# RoboShield.net
KiCad netlist of a schematic drawn in EAGLE
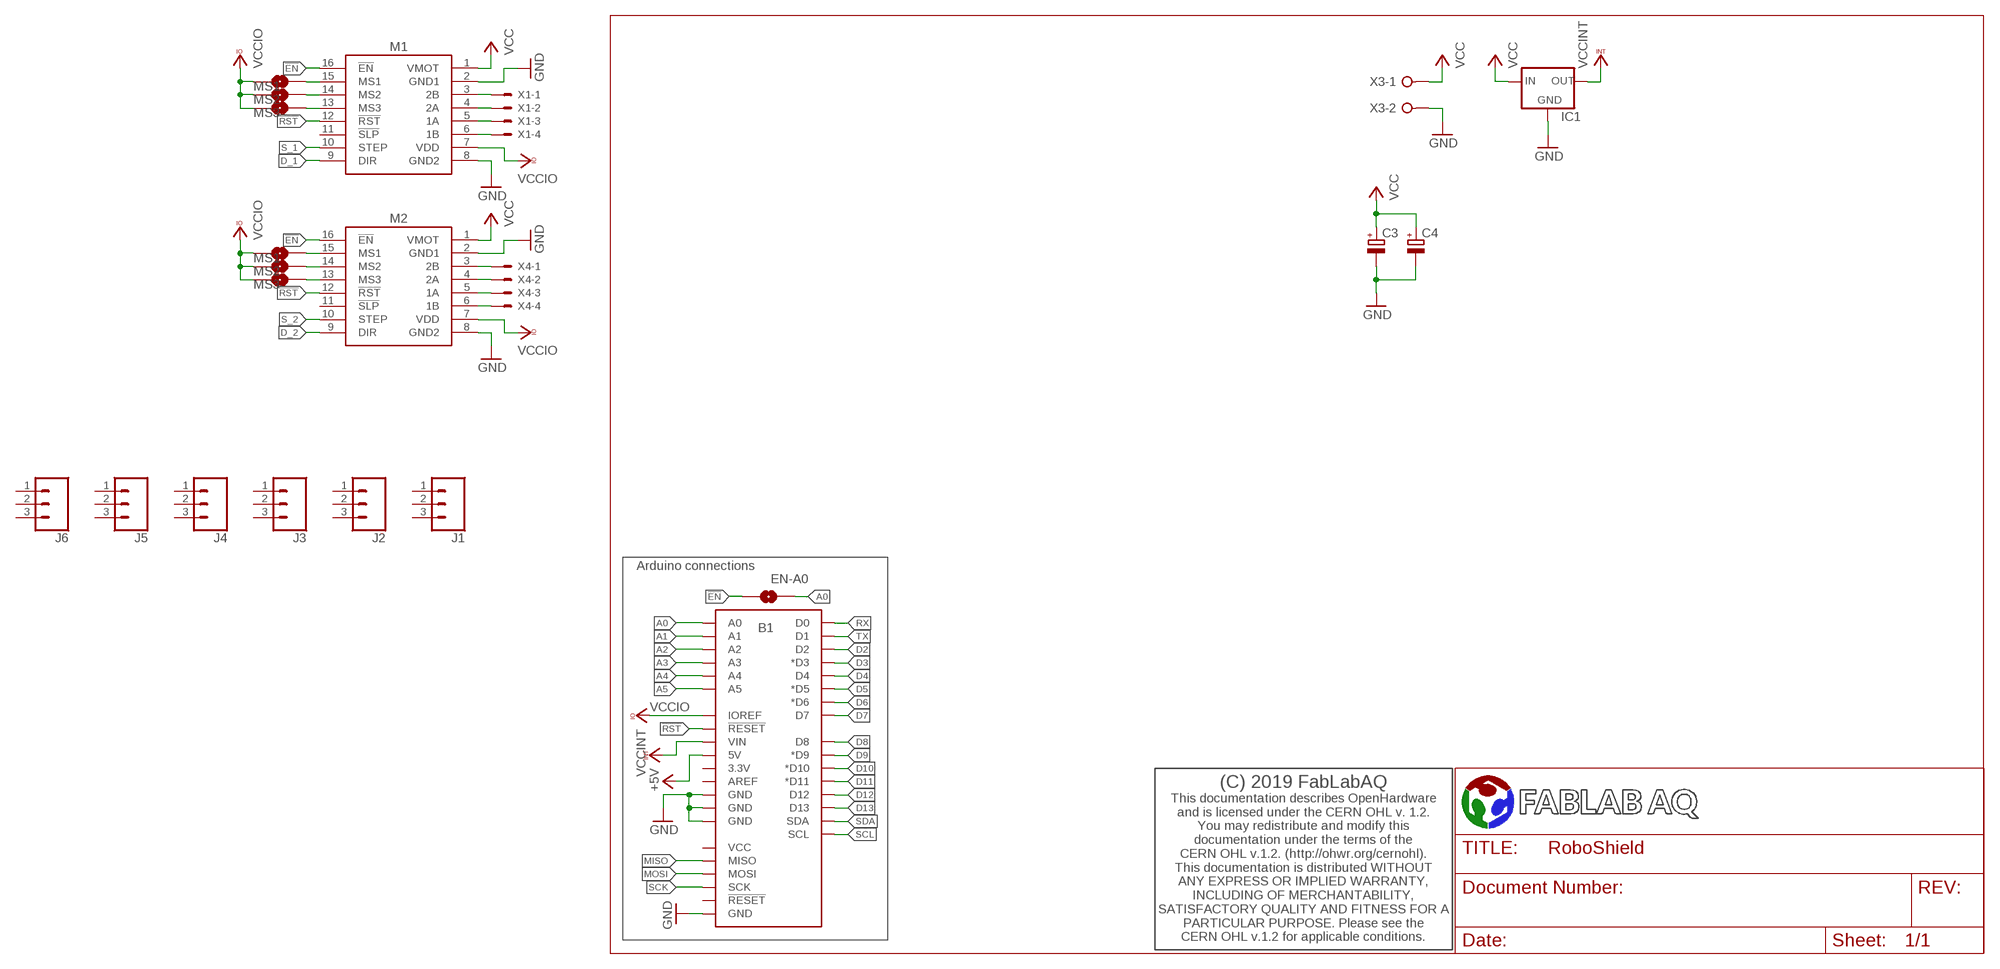
[diagram p0: schematic, sheet 1]

(export (version "E")
  (design (tool "Eeschema 10.0.6"))
  (components
    (comp (ref "B1")
      (value "ARDUINO_UNO_R3NO_HOLES")
      (footprint "eagle-import:ARDUINO_R3_NO_HOLES")
      (libsource (lib "eagle-import") (part "ARDUINO_UNO_R3NO_HOLES"))
    )
    (comp (ref "C3")
      (value "CPOL-EUUD-8X10")
      (footprint "eagle-import:UD-8X10_NICHICON")
      (libsource (lib "eagle-import") (part "CPOL-EUUD-8X10"))
    )
    (comp (ref "C4")
      (value "CPOL-EUE3.5-8")
      (footprint "eagle-import:E3,5-8")
      (libsource (lib "eagle-import") (part "rcl_334_CPOL-EUE3.5-8"))
    )
    (comp (ref "IC1")
      (value "78XXS")
      (footprint "eagle-import:78XXS")
      (libsource (lib "eagle-import") (part "78XXS"))
    )
    (comp (ref "J1")
      (value "CONN_03")
      (footprint "eagle-import:1X03")
      (libsource (lib "eagle-import") (part "CONN_03"))
    )
    (comp (ref "J2")
      (value "CONN_03")
      (footprint "eagle-import:1X03")
      (libsource (lib "eagle-import") (part "CONN_03"))
    )
    (comp (ref "J3")
      (value "CONN_03")
      (footprint "eagle-import:1X03")
      (libsource (lib "eagle-import") (part "CONN_03"))
    )
    (comp (ref "J4")
      (value "CONN_03")
      (footprint "eagle-import:1X03")
      (libsource (lib "eagle-import") (part "CONN_03"))
    )
    (comp (ref "J5")
      (value "CONN_03")
      (footprint "eagle-import:1X03")
      (libsource (lib "eagle-import") (part "CONN_03"))
    )
    (comp (ref "J6")
      (value "CONN_03")
      (footprint "eagle-import:1X03")
      (libsource (lib "eagle-import") (part "CONN_03"))
    )
    (comp (ref "JP1")
      (value "MS1")
      (footprint "eagle-import:SMT-JUMPER_2_NO_SILK")
      (libsource (lib "eagle-import") (part "JUMPER-SMT_2_NO_SILK"))
    )
    (comp (ref "JP2")
      (value "MS2")
      (footprint "eagle-import:SMT-JUMPER_2_NO_SILK")
      (libsource (lib "eagle-import") (part "JUMPER-SMT_2_NO_SILK"))
    )
    (comp (ref "JP3")
      (value "MS3")
      (footprint "eagle-import:SMT-JUMPER_2_NO_SILK")
      (libsource (lib "eagle-import") (part "JUMPER-SMT_2_NO_SILK"))
    )
    (comp (ref "JP4")
      (value "EN-A0")
      (footprint "eagle-import:SMT-JUMPER_2_NO_SILK")
      (libsource (lib "eagle-import") (part "JUMPER-SMT_2_NO_SILK"))
    )
    (comp (ref "JP5")
      (value "MS1")
      (footprint "eagle-import:SMT-JUMPER_2_NO_SILK")
      (libsource (lib "eagle-import") (part "JUMPER-SMT_2_NO_SILK"))
    )
    (comp (ref "JP6")
      (value "MS2")
      (footprint "eagle-import:SMT-JUMPER_2_NO_SILK")
      (libsource (lib "eagle-import") (part "JUMPER-SMT_2_NO_SILK"))
    )
    (comp (ref "JP7")
      (value "MS3")
      (footprint "eagle-import:SMT-JUMPER_2_NO_SILK")
      (libsource (lib "eagle-import") (part "JUMPER-SMT_2_NO_SILK"))
    )
    (comp (ref "M1")
      (value "POLOLUESTEPPERDRIVER")
      (footprint "eagle-import:DIL16")
      (libsource (lib "eagle-import") (part "POLOLUESTEPPERDRIVER"))
    )
    (comp (ref "M2")
      (value "POLOLUESTEPPERDRIVER")
      (footprint "eagle-import:DIL16")
      (libsource (lib "eagle-import") (part "POLOLUESTEPPERDRIVER"))
    )
    (comp (ref "U$2")
      (value "(C) 2019 FabLabAQ")
      (footprint "eagle-import:DOC_CERN_OHL_1.2")
      (libsource (lib "eagle-import") (part "CERN_OHL_1.2"))
    )
    (comp (ref "U$3")
      (value "FABLABAQ_LOGOCENTER_20X40")
      (footprint "eagle-import:SILK_CENTER_20X40")
      (libsource (lib "eagle-import") (part "FABLABAQ_LOGOCENTER_20X40"))
    )
    (comp (ref "X1")
      (value "JST-XH-04-PIN-LONG-PAD")
      (footprint "eagle-import:JST-XH-04-PACKAGE-LONG-PAD")
      (libsource (lib "eagle-import") (part "JST-XH-04-PIN-LONG-PAD"))
    )
    (comp (ref "X3")
      (value "W237-02P")
      (footprint "eagle-import:W237-132")
      (libsource (lib "eagle-import") (part "W237-02P"))
    )
    (comp (ref "X4")
      (value "JST-XH-04-PIN-LONG-PAD")
      (footprint "eagle-import:JST-XH-04-PACKAGE-LONG-PAD")
      (libsource (lib "eagle-import") (part "JST-XH-04-PIN-LONG-PAD"))
    )
  )
  (nets
    (net (code "1") (name "+5V") (class "Default")
      (node (ref "B1") (pin "5V") (pinfunction "5V_5V") (pintype "bidirectional"))
    )
    (net (code "2") (name "/~{EN}") (class "Default")
      (node (ref "JP4") (pin "1") (pinfunction "1_1") (pintype "passive"))
      (node (ref "M1") (pin "16") (pinfunction "~{EN}_16") (pintype "input"))
      (node (ref "M2") (pin "16") (pinfunction "~{EN}_16") (pintype "input"))
    )
    (net (code "3") (name "/~{RST}") (class "Default")
      (node (ref "B1") (pin "RESET@1") (pinfunction "~{RESET}_RESET@1") (pintype "bidirectional"))
      (node (ref "M1") (pin "12") (pinfunction "~{RST}_12") (pintype "input"))
      (node (ref "M2") (pin "12") (pinfunction "~{RST}_12") (pintype "input"))
    )
    (net (code "4") (name "A0") (class "Default")
      (node (ref "B1") (pin "A0") (pinfunction "A0_A0") (pintype "bidirectional"))
      (node (ref "JP4") (pin "2") (pinfunction "2_2") (pintype "passive"))
    )
    (net (code "5") (name "A1") (class "Default")
      (node (ref "B1") (pin "A1") (pinfunction "A1_A1") (pintype "bidirectional"))
    )
    (net (code "6") (name "A2") (class "Default")
      (node (ref "B1") (pin "A2") (pinfunction "A2_A2") (pintype "bidirectional"))
    )
    (net (code "7") (name "A3") (class "Default")
      (node (ref "B1") (pin "A3") (pinfunction "A3_A3") (pintype "bidirectional"))
    )
    (net (code "8") (name "A4") (class "Default")
      (node (ref "B1") (pin "A4") (pinfunction "A4_A4") (pintype "bidirectional"))
    )
    (net (code "9") (name "A5") (class "Default")
      (node (ref "B1") (pin "A5") (pinfunction "A5_A5") (pintype "bidirectional"))
    )
    (net (code "10") (name "D2") (class "Default")
      (node (ref "B1") (pin "D2") (pinfunction "D2_D2") (pintype "bidirectional"))
    )
    (net (code "11") (name "D3") (class "Default")
      (node (ref "B1") (pin "D3") (pinfunction "*D3_D3") (pintype "bidirectional"))
    )
    (net (code "12") (name "D4") (class "Default")
      (node (ref "B1") (pin "D4") (pinfunction "D4_D4") (pintype "bidirectional"))
    )
    (net (code "13") (name "D5") (class "Default")
      (node (ref "B1") (pin "D5") (pinfunction "*D5_D5") (pintype "bidirectional"))
    )
    (net (code "14") (name "D6") (class "Default")
      (node (ref "B1") (pin "D6") (pinfunction "*D6_D6") (pintype "bidirectional"))
    )
    (net (code "15") (name "D7") (class "Default")
      (node (ref "B1") (pin "D7") (pinfunction "D7_D7") (pintype "bidirectional"))
    )
    (net (code "16") (name "D8") (class "Default")
      (node (ref "B1") (pin "D8") (pinfunction "D8_D8") (pintype "bidirectional"))
    )
    (net (code "17") (name "D9") (class "Default")
      (node (ref "B1") (pin "D9") (pinfunction "*D9_D9") (pintype "bidirectional"))
    )
    (net (code "18") (name "D10") (class "Default")
      (node (ref "B1") (pin "D10") (pinfunction "*D10_D10") (pintype "bidirectional"))
    )
    (net (code "19") (name "D11") (class "Default")
      (node (ref "B1") (pin "D11") (pinfunction "*D11_D11") (pintype "bidirectional"))
    )
    (net (code "20") (name "D12") (class "Default")
      (node (ref "B1") (pin "D12") (pinfunction "D12_D12") (pintype "bidirectional"))
    )
    (net (code "21") (name "D13") (class "Default")
      (node (ref "B1") (pin "D13") (pinfunction "D13_D13") (pintype "bidirectional"))
    )
    (net (code "22") (name "D_1") (class "Default")
      (node (ref "M1") (pin "9") (pinfunction "DIR_9") (pintype "input"))
    )
    (net (code "23") (name "D_2") (class "Default")
      (node (ref "M2") (pin "9") (pinfunction "DIR_9") (pintype "input"))
    )
    (net (code "24") (name "GND") (class "Default")
      (node (ref "B1") (pin "GND@1") (pinfunction "GND_GND@1") (pintype "bidirectional"))
      (node (ref "B1") (pin "GND@2") (pinfunction "GND_GND@2") (pintype "bidirectional"))
      (node (ref "B1") (pin "GND@3") (pinfunction "GND_GND@3") (pintype "bidirectional"))
      (node (ref "B1") (pin "GND@4") (pinfunction "GND_GND@4") (pintype "bidirectional"))
      (node (ref "C3") (pin "-") (pinfunction "-_-") (pintype "passive"))
      (node (ref "C4") (pin "-") (pinfunction "-_-") (pintype "passive"))
      (node (ref "IC1") (pin "GND") (pinfunction "GND_GND") (pintype "input"))
      (node (ref "M1") (pin "2") (pinfunction "GND1_2") (pintype "power_in"))
      (node (ref "M1") (pin "8") (pinfunction "GND2_8") (pintype "power_in"))
      (node (ref "M2") (pin "2") (pinfunction "GND1_2") (pintype "power_in"))
      (node (ref "M2") (pin "8") (pinfunction "GND2_8") (pintype "power_in"))
      (node (ref "X3") (pin "2") (pinfunction "KL_2") (pintype "passive"))
    )
    (net (code "25") (name "MISO") (class "Default")
      (node (ref "B1") (pin "MISO") (pinfunction "MISO_MISO") (pintype "bidirectional"))
    )
    (net (code "26") (name "MOSI") (class "Default")
      (node (ref "B1") (pin "MOSI") (pinfunction "MOSI_MOSI") (pintype "bidirectional"))
    )
    (net (code "27") (name "Net-(M1-1A)") (class "Default")
      (node (ref "M1") (pin "5") (pinfunction "1A_5") (pintype "output"))
      (node (ref "X1") (pin "3") (pinfunction "S_3") (pintype "passive"))
    )
    (net (code "28") (name "Net-(M1-1B)") (class "Default")
      (node (ref "M1") (pin "6") (pinfunction "1B_6") (pintype "output"))
      (node (ref "X1") (pin "4") (pinfunction "S_4") (pintype "passive"))
    )
    (net (code "29") (name "Net-(M1-2A)") (class "Default")
      (node (ref "M1") (pin "4") (pinfunction "2A_4") (pintype "output"))
      (node (ref "X1") (pin "2") (pinfunction "S_2") (pintype "passive"))
    )
    (net (code "30") (name "Net-(M1-2B)") (class "Default")
      (node (ref "M1") (pin "3") (pinfunction "2B_3") (pintype "output"))
      (node (ref "X1") (pin "1") (pinfunction "S_1") (pintype "passive"))
    )
    (net (code "31") (name "Net-(M1-MS1)") (class "Default")
      (node (ref "JP1") (pin "2") (pinfunction "2_2") (pintype "passive"))
      (node (ref "M1") (pin "15") (pinfunction "MS1_15") (pintype "input"))
    )
    (net (code "32") (name "Net-(M1-MS2)") (class "Default")
      (node (ref "JP2") (pin "2") (pinfunction "2_2") (pintype "passive"))
      (node (ref "M1") (pin "14") (pinfunction "MS2_14") (pintype "input"))
    )
    (net (code "33") (name "Net-(M1-MS3)") (class "Default")
      (node (ref "JP3") (pin "2") (pinfunction "2_2") (pintype "passive"))
      (node (ref "M1") (pin "13") (pinfunction "MS3_13") (pintype "input"))
    )
    (net (code "34") (name "Net-(M2-1A)") (class "Default")
      (node (ref "M2") (pin "5") (pinfunction "1A_5") (pintype "output"))
      (node (ref "X4") (pin "3") (pinfunction "S_3") (pintype "passive"))
    )
    (net (code "35") (name "Net-(M2-1B)") (class "Default")
      (node (ref "M2") (pin "6") (pinfunction "1B_6") (pintype "output"))
      (node (ref "X4") (pin "4") (pinfunction "S_4") (pintype "passive"))
    )
    (net (code "36") (name "Net-(M2-2A)") (class "Default")
      (node (ref "M2") (pin "4") (pinfunction "2A_4") (pintype "output"))
      (node (ref "X4") (pin "2") (pinfunction "S_2") (pintype "passive"))
    )
    (net (code "37") (name "Net-(M2-2B)") (class "Default")
      (node (ref "M2") (pin "3") (pinfunction "2B_3") (pintype "output"))
      (node (ref "X4") (pin "1") (pinfunction "S_1") (pintype "passive"))
    )
    (net (code "38") (name "Net-(M2-MS1)") (class "Default")
      (node (ref "JP5") (pin "2") (pinfunction "2_2") (pintype "passive"))
      (node (ref "M2") (pin "15") (pinfunction "MS1_15") (pintype "input"))
    )
    (net (code "39") (name "Net-(M2-MS2)") (class "Default")
      (node (ref "JP6") (pin "2") (pinfunction "2_2") (pintype "passive"))
      (node (ref "M2") (pin "14") (pinfunction "MS2_14") (pintype "input"))
    )
    (net (code "40") (name "Net-(M2-MS3)") (class "Default")
      (node (ref "JP7") (pin "2") (pinfunction "2_2") (pintype "passive"))
      (node (ref "M2") (pin "13") (pinfunction "MS3_13") (pintype "input"))
    )
    (net (code "41") (name "RX") (class "Default")
      (node (ref "B1") (pin "D0") (pinfunction "D0_D0") (pintype "bidirectional"))
    )
    (net (code "42") (name "SCK") (class "Default")
      (node (ref "B1") (pin "SCK") (pinfunction "SCK_SCK") (pintype "bidirectional"))
    )
    (net (code "43") (name "SCL") (class "Default")
      (node (ref "B1") (pin "SCL") (pinfunction "SCL_SCL") (pintype "bidirectional"))
    )
    (net (code "44") (name "SDA") (class "Default")
      (node (ref "B1") (pin "SDA") (pinfunction "SDA_SDA") (pintype "bidirectional"))
    )
    (net (code "45") (name "S_1") (class "Default")
      (node (ref "M1") (pin "10") (pinfunction "STEP_10") (pintype "input"))
    )
    (net (code "46") (name "S_2") (class "Default")
      (node (ref "M2") (pin "10") (pinfunction "STEP_10") (pintype "input"))
    )
    (net (code "47") (name "TX") (class "Default")
      (node (ref "B1") (pin "D1") (pinfunction "D1_D1") (pintype "bidirectional"))
    )
    (net (code "48") (name "VCC") (class "Default")
      (node (ref "C3") (pin "+") (pinfunction "+_+") (pintype "passive"))
      (node (ref "C4") (pin "+") (pinfunction "+_+") (pintype "passive"))
      (node (ref "IC1") (pin "IN") (pinfunction "IN_IN") (pintype "input"))
      (node (ref "M1") (pin "1") (pinfunction "VMOT_1") (pintype "power_in"))
      (node (ref "M2") (pin "1") (pinfunction "VMOT_1") (pintype "power_in"))
      (node (ref "X3") (pin "1") (pinfunction "KL_1") (pintype "passive"))
    )
    (net (code "49") (name "VCCINT") (class "Default")
      (node (ref "B1") (pin "VIN") (pinfunction "VIN_VIN") (pintype "bidirectional"))
      (node (ref "IC1") (pin "OUT") (pinfunction "OUT_OUT") (pintype "passive"))
    )
    (net (code "50") (name "VCCIO") (class "Default")
      (node (ref "B1") (pin "IOREF") (pinfunction "IOREF_IOREF") (pintype "bidirectional"))
      (node (ref "JP1") (pin "1") (pinfunction "1_1") (pintype "passive"))
      (node (ref "JP2") (pin "1") (pinfunction "1_1") (pintype "passive"))
      (node (ref "JP3") (pin "1") (pinfunction "1_1") (pintype "passive"))
      (node (ref "JP5") (pin "1") (pinfunction "1_1") (pintype "passive"))
      (node (ref "JP6") (pin "1") (pinfunction "1_1") (pintype "passive"))
      (node (ref "JP7") (pin "1") (pinfunction "1_1") (pintype "passive"))
      (node (ref "M1") (pin "7") (pinfunction "VDD_7") (pintype "power_in"))
      (node (ref "M2") (pin "7") (pinfunction "VDD_7") (pintype "power_in"))
    )
    (net (code "51") (name "unconnected-(B1-Pad3.3V)") (class "Default")
      (node (ref "B1") (pin "3.3V") (pinfunction "3.3V_3.3V") (pintype "bidirectional"))
    )
    (net (code "52") (name "unconnected-(B1-PadAREF)") (class "Default")
      (node (ref "B1") (pin "AREF") (pinfunction "AREF_AREF") (pintype "bidirectional"))
    )
    (net (code "53") (name "unconnected-(B1-PadVCC)") (class "Default")
      (node (ref "B1") (pin "VCC") (pinfunction "VCC_VCC") (pintype "bidirectional"))
    )
    (net (code "54") (name "unconnected-(B1-~{RESET}-PadRESET@2)") (class "Default")
      (node (ref "B1") (pin "RESET@2") (pinfunction "~{RESET}_RESET@2") (pintype "bidirectional"))
    )
    (net (code "55") (name "unconnected-(J1-Pad1)") (class "Default")
      (node (ref "J1") (pin "1") (pinfunction "1_1") (pintype "passive"))
    )
    (net (code "56") (name "unconnected-(J1-Pad2)") (class "Default")
      (node (ref "J1") (pin "2") (pinfunction "2_2") (pintype "passive"))
    )
    (net (code "57") (name "unconnected-(J1-Pad3)") (class "Default")
      (node (ref "J1") (pin "3") (pinfunction "3_3") (pintype "passive"))
    )
    (net (code "58") (name "unconnected-(J2-Pad1)") (class "Default")
      (node (ref "J2") (pin "1") (pinfunction "1_1") (pintype "passive"))
    )
    (net (code "59") (name "unconnected-(J2-Pad2)") (class "Default")
      (node (ref "J2") (pin "2") (pinfunction "2_2") (pintype "passive"))
    )
    (net (code "60") (name "unconnected-(J2-Pad3)") (class "Default")
      (node (ref "J2") (pin "3") (pinfunction "3_3") (pintype "passive"))
    )
    (net (code "61") (name "unconnected-(J3-Pad1)") (class "Default")
      (node (ref "J3") (pin "1") (pinfunction "1_1") (pintype "passive"))
    )
    (net (code "62") (name "unconnected-(J3-Pad2)") (class "Default")
      (node (ref "J3") (pin "2") (pinfunction "2_2") (pintype "passive"))
    )
    (net (code "63") (name "unconnected-(J3-Pad3)") (class "Default")
      (node (ref "J3") (pin "3") (pinfunction "3_3") (pintype "passive"))
    )
    (net (code "64") (name "unconnected-(J4-Pad1)") (class "Default")
      (node (ref "J4") (pin "1") (pinfunction "1_1") (pintype "passive"))
    )
    (net (code "65") (name "unconnected-(J4-Pad2)") (class "Default")
      (node (ref "J4") (pin "2") (pinfunction "2_2") (pintype "passive"))
    )
    (net (code "66") (name "unconnected-(J4-Pad3)") (class "Default")
      (node (ref "J4") (pin "3") (pinfunction "3_3") (pintype "passive"))
    )
    (net (code "67") (name "unconnected-(J5-Pad1)") (class "Default")
      (node (ref "J5") (pin "1") (pinfunction "1_1") (pintype "passive"))
    )
    (net (code "68") (name "unconnected-(J5-Pad2)") (class "Default")
      (node (ref "J5") (pin "2") (pinfunction "2_2") (pintype "passive"))
    )
    (net (code "69") (name "unconnected-(J5-Pad3)") (class "Default")
      (node (ref "J5") (pin "3") (pinfunction "3_3") (pintype "passive"))
    )
    (net (code "70") (name "unconnected-(J6-Pad1)") (class "Default")
      (node (ref "J6") (pin "1") (pinfunction "1_1") (pintype "passive"))
    )
    (net (code "71") (name "unconnected-(J6-Pad2)") (class "Default")
      (node (ref "J6") (pin "2") (pinfunction "2_2") (pintype "passive"))
    )
    (net (code "72") (name "unconnected-(J6-Pad3)") (class "Default")
      (node (ref "J6") (pin "3") (pinfunction "3_3") (pintype "passive"))
    )
    (net (code "73") (name "unconnected-(M1-~{SLP}-Pad11)") (class "Default")
      (node (ref "M1") (pin "11") (pinfunction "~{SLP}_11") (pintype "input"))
    )
    (net (code "74") (name "unconnected-(M2-~{SLP}-Pad11)") (class "Default")
      (node (ref "M2") (pin "11") (pinfunction "~{SLP}_11") (pintype "input"))
    )
  )
)
